# 2021_06_29_V7.net
KiCad netlist of a schematic drawn in EAGLE
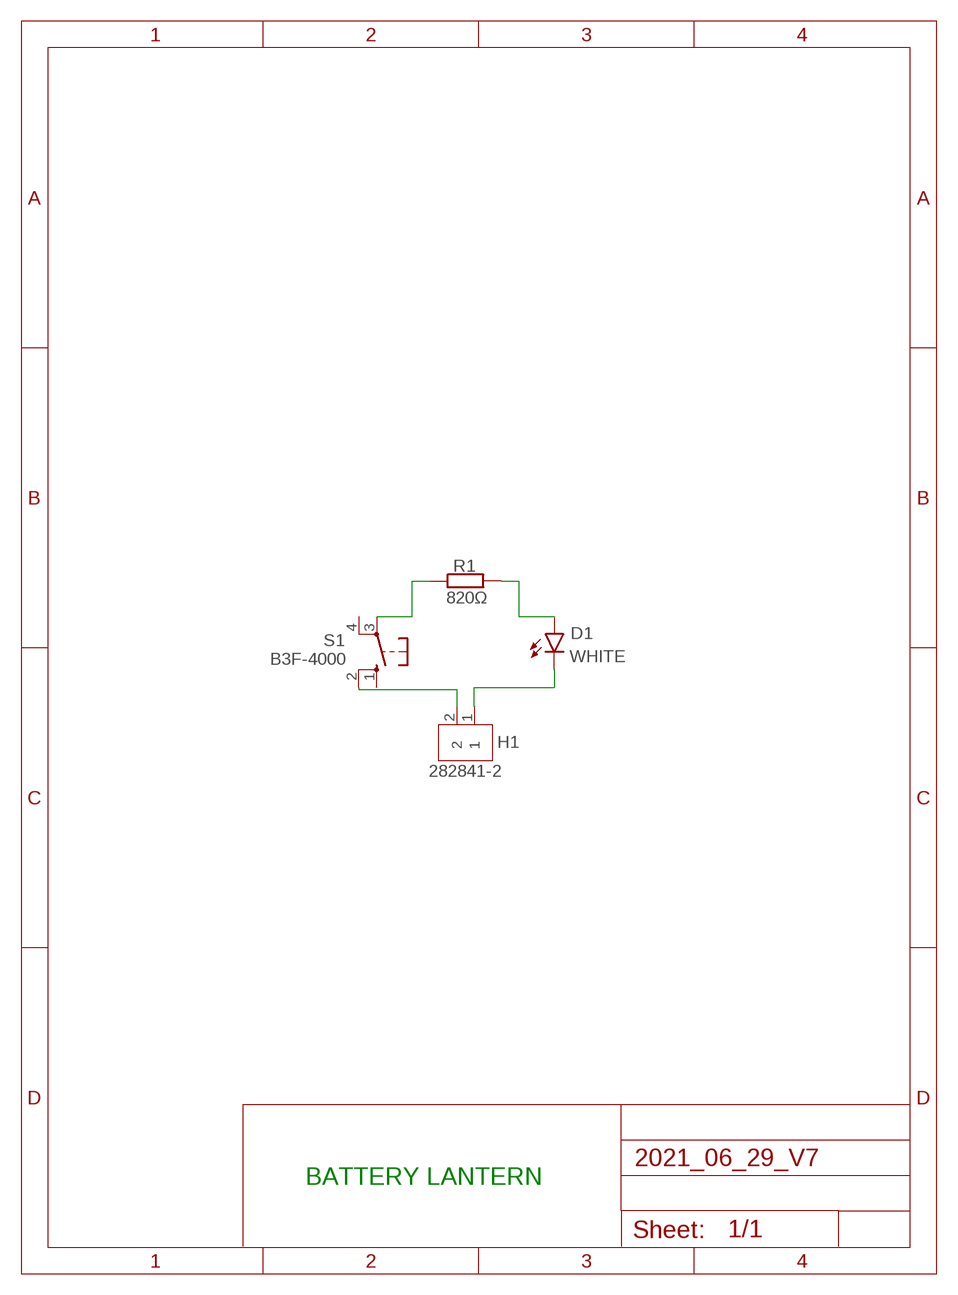
[diagram p0: schematic, sheet 1]

(export (version "E")
  (design (tool "Eeschema 10.0.6"))
  (components
    (comp (ref "D1")
      (value "WHITE")
      (footprint "eagle-import:LEDRD254W60D565H860B_W")
      (libsource (lib "eagle-import") (part "LED_RADIALWHITE_"))
    )
    (comp (ref "H1")
      (value "282841-2")
      (footprint "eagle-import:TERMBLK_508-2N")
      (fields (field (name "MANUFACTURER") "TE Connectivity") (field (name "MPN") "282837-2"))
      (libsource (lib "eagle-import") (part "2828XX-2282837-2"))
    )
    (comp (ref "R1")
      (value "820Ω")
      (footprint "eagle-import:0207_7")
      (libsource (lib "eagle-import") (part "R-EU_0207/7"))
    )
    (comp (ref "S1")
      (value "B3F-4000")
      (footprint "eagle-import:B3F-40XX")
      (fields (field (name "MF") "OMRON COMPONENTS USA"))
      (libsource (lib "eagle-import") (part "40-XX"))
    )
  )
  (nets
    (net (code "1") (name "Net-(D1-A)") (class "Default")
      (node (ref "D1") (pin "1") (pinfunction "A_1") (pintype "passive"))
      (node (ref "R1") (pin "2") (pinfunction "2_2") (pintype "passive"))
    )
    (net (code "2") (name "Net-(D1-C)") (class "Default")
      (node (ref "D1") (pin "2") (pinfunction "C_2") (pintype "passive"))
      (node (ref "H1") (pin "1") (pinfunction "1_1") (pintype "bidirectional"))
    )
    (net (code "3") (name "Net-(S1-P)") (class "Default")
      (node (ref "R1") (pin "1") (pinfunction "1_1") (pintype "passive"))
      (node (ref "S1") (pin "3") (pinfunction "P_3") (pintype "passive"))
    )
    (net (code "4") (name "Net-(S1-S1)") (class "Default")
      (node (ref "H1") (pin "2") (pinfunction "2_2") (pintype "bidirectional"))
      (node (ref "S1") (pin "2") (pinfunction "S1_2") (pintype "passive"))
    )
    (net (code "5") (name "unconnected-(S1-P1-Pad4)") (class "Default")
      (node (ref "S1") (pin "4") (pinfunction "P1_4") (pintype "passive"))
    )
    (net (code "6") (name "unconnected-(S1-S-Pad1)") (class "Default")
      (node (ref "S1") (pin "1") (pinfunction "S_1") (pintype "passive"))
    )
  )
)
